# IR_MOD.net
KiCad netlist of a schematic drawn in Altium Designer
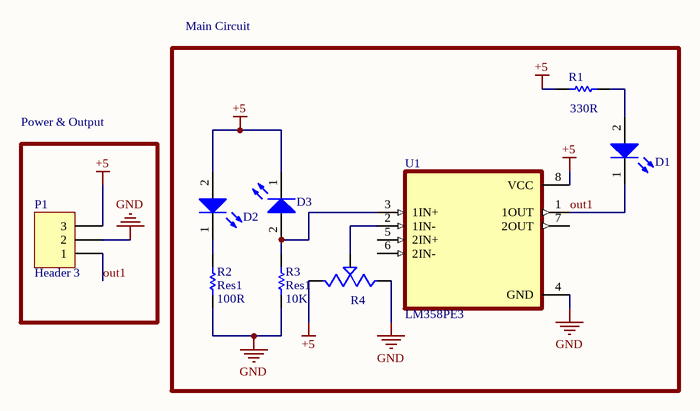
[diagram p0: IR_MOD.SchDoc]

(export (version "E")
  (design (tool "Eeschema 10.0.6"))
  (components
    (comp (ref "D1")
      (value "Infrared, 1.5V, 35°")
      (footprint "WL-TIRW_D3.9H5.3")
      (description "WL-TIRW THT Infrared Round Waterclear, D3.9 x H5.3mm, 60mW/sr, Infrared, 1.5V, 35°")
      (fields
        (field (name "MANUFACTURER PART NUMBER") "15400385A3590")
        (field (name "MANUFACTURER") "Wurth Elektronik")
      )
      (libsource (lib "WL-TIRW") (part "15400385A3590"))
    )
    (comp (ref "D2")
      (value "Infrared, 1.5V, 35°")
      (footprint "WL-TIRW_D3.9H5.3")
      (description "WL-TIRW THT Infrared Round Waterclear, D3.9 x H5.3mm, 60mW/sr, Infrared, 1.5V, 35°")
      (fields
        (field (name "MANUFACTURER PART NUMBER") "15400385A3590")
        (field (name "MANUFACTURER") "Wurth Elektronik")
      )
      (libsource (lib "WL-TIRW") (part "15400385A3590"))
    )
    (comp (ref "D3")
      (value "Infrared, 1.5V, 35°")
      (footprint "WL-TIRW_D3.9H5.3")
      (description "WL-TIRW THT Infrared Round Waterclear, D3.9 x H5.3mm, 60mW/sr, Infrared, 1.5V, 35°")
      (fields
        (field (name "MANUFACTURER PART NUMBER") "15400385A3590")
        (field (name "MANUFACTURER") "Wurth Elektronik")
      )
      (libsource (lib "WL-TIRW") (part "15400385A3590"))
    )
    (comp (ref "P1")
      (value "Header 3")
      (footprint "HDR1X3")
      (description "Header, 3-Pin")
      (fields (field (name "PUBLISHER") "Altium Limited"))
      (libsource (lib "Miscellaneous Connectors") (part "Header 3"))
    )
    (comp (ref "R1")
      (value "330R")
      (footprint "AXIAL-0.3")
      (description "Resistor")
      (fields (field (name "Comment") "100R") (field (name "PUBLISHER") "Altium Limited"))
      (libsource (lib "Miscellaneous Devices") (part "Res1"))
    )
    (comp (ref "R2")
      (value "Res1")
      (footprint "AXIAL-0.3")
      (description "Resistor")
      (fields (field (name "ALTIUM_VALUE") "100R") (field (name "PUBLISHER") "Altium Limited"))
      (libsource (lib "Miscellaneous Devices") (part "Res1"))
    )
    (comp (ref "R3")
      (value "Res1")
      (footprint "AXIAL-0.3")
      (description "Resistor")
      (fields (field (name "ALTIUM_VALUE") "10K") (field (name "PUBLISHER") "Altium Limited"))
      (libsource (lib "Miscellaneous Devices") (part "Res1"))
    )
    (comp (ref "R4")
      (value "~")
      (footprint "TRIM_EVN-D8AA03B55")
      (description "500 kOhms 0.1W, 1/10W PC Pins Through Hole Trimmer Potentiometer Carbon 1.0 Turn Top Adjustment")
      (fields (field (name "MF") "Panasonic Electronic") (field (name "MP") "EVN-D8AA03B55"))
      (libsource (lib "EVN-D8AA03B55") (part "EVN-D8AA03B55"))
    )
    (comp (ref "U1")
      (value "LM358PE3")
      (footprint "DIP794W45P254L959H508Q8:DIP794W45P254L959H508Q8")
      (libsource (lib "LM358PE3") (part "LM358PE3"))
    )
  )
  (nets
    (net (code "1") (name "+5") (class "Default")
      (node (ref "D2") (pin "2") (pinfunction "A_2") (pintype "passive"))
      (node (ref "D3") (pin "1") (pinfunction "K_1") (pintype "passive"))
      (node (ref "P1") (pin "3") (pinfunction "3_3") (pintype "passive"))
      (node (ref "R1") (pin "2") (pinfunction "2_2") (pintype "passive"))
      (node (ref "R4") (pin "3") (pinfunction "3_3") (pintype "passive"))
      (node (ref "U1") (pin "8") (pinfunction "VCC_8") (pintype "power_in"))
    )
    (net (code "2") (name "/out1") (class "Default")
      (node (ref "D1") (pin "1") (pinfunction "K_1") (pintype "passive"))
      (node (ref "P1") (pin "1") (pinfunction "1_1") (pintype "passive"))
      (node (ref "U1") (pin "1") (pinfunction "1OUT_1") (pintype "output"))
    )
    (net (code "3") (name "GND") (class "Default")
      (node (ref "P1") (pin "2") (pinfunction "2_2") (pintype "passive"))
      (node (ref "R2") (pin "1") (pinfunction "1_1") (pintype "passive"))
      (node (ref "R3") (pin "1") (pinfunction "1_1") (pintype "passive"))
      (node (ref "R4") (pin "1") (pinfunction "1_1") (pintype "passive"))
      (node (ref "U1") (pin "4") (pinfunction "GND_4") (pintype "power_in"))
    )
    (net (code "4") (name "Net-(D1-A)") (class "Default")
      (node (ref "D1") (pin "2") (pinfunction "A_2") (pintype "passive"))
      (node (ref "R1") (pin "1") (pinfunction "1_1") (pintype "passive"))
    )
    (net (code "5") (name "Net-(D2-K)") (class "Default")
      (node (ref "D2") (pin "1") (pinfunction "K_1") (pintype "passive"))
      (node (ref "R2") (pin "2") (pinfunction "2_2") (pintype "passive"))
    )
    (net (code "6") (name "Net-(D3-A)") (class "Default")
      (node (ref "D3") (pin "2") (pinfunction "A_2") (pintype "passive"))
      (node (ref "R3") (pin "2") (pinfunction "2_2") (pintype "passive"))
      (node (ref "U1") (pin "3") (pinfunction "1IN+_3") (pintype "input"))
    )
    (net (code "7") (name "Net-(U1-1IN-)") (class "Default")
      (node (ref "R4") (pin "2") (pinfunction "2_2") (pintype "passive"))
      (node (ref "U1") (pin "2") (pinfunction "1IN-_2") (pintype "input"))
    )
    (net (code "8") (name "unconnected-(U1-2IN+-Pad5)") (class "Default")
      (node (ref "U1") (pin "5") (pinfunction "2IN+_5") (pintype "input"))
    )
    (net (code "9") (name "unconnected-(U1-2IN--Pad6)") (class "Default")
      (node (ref "U1") (pin "6") (pinfunction "2IN-_6") (pintype "input"))
    )
    (net (code "10") (name "unconnected-(U1-2OUT-Pad7)") (class "Default")
      (node (ref "U1") (pin "7") (pinfunction "2OUT_7") (pintype "output"))
    )
  )
)
